# Quad_FC_power_V10_7-final.net
KiCad netlist of a schematic drawn in Altium Designer
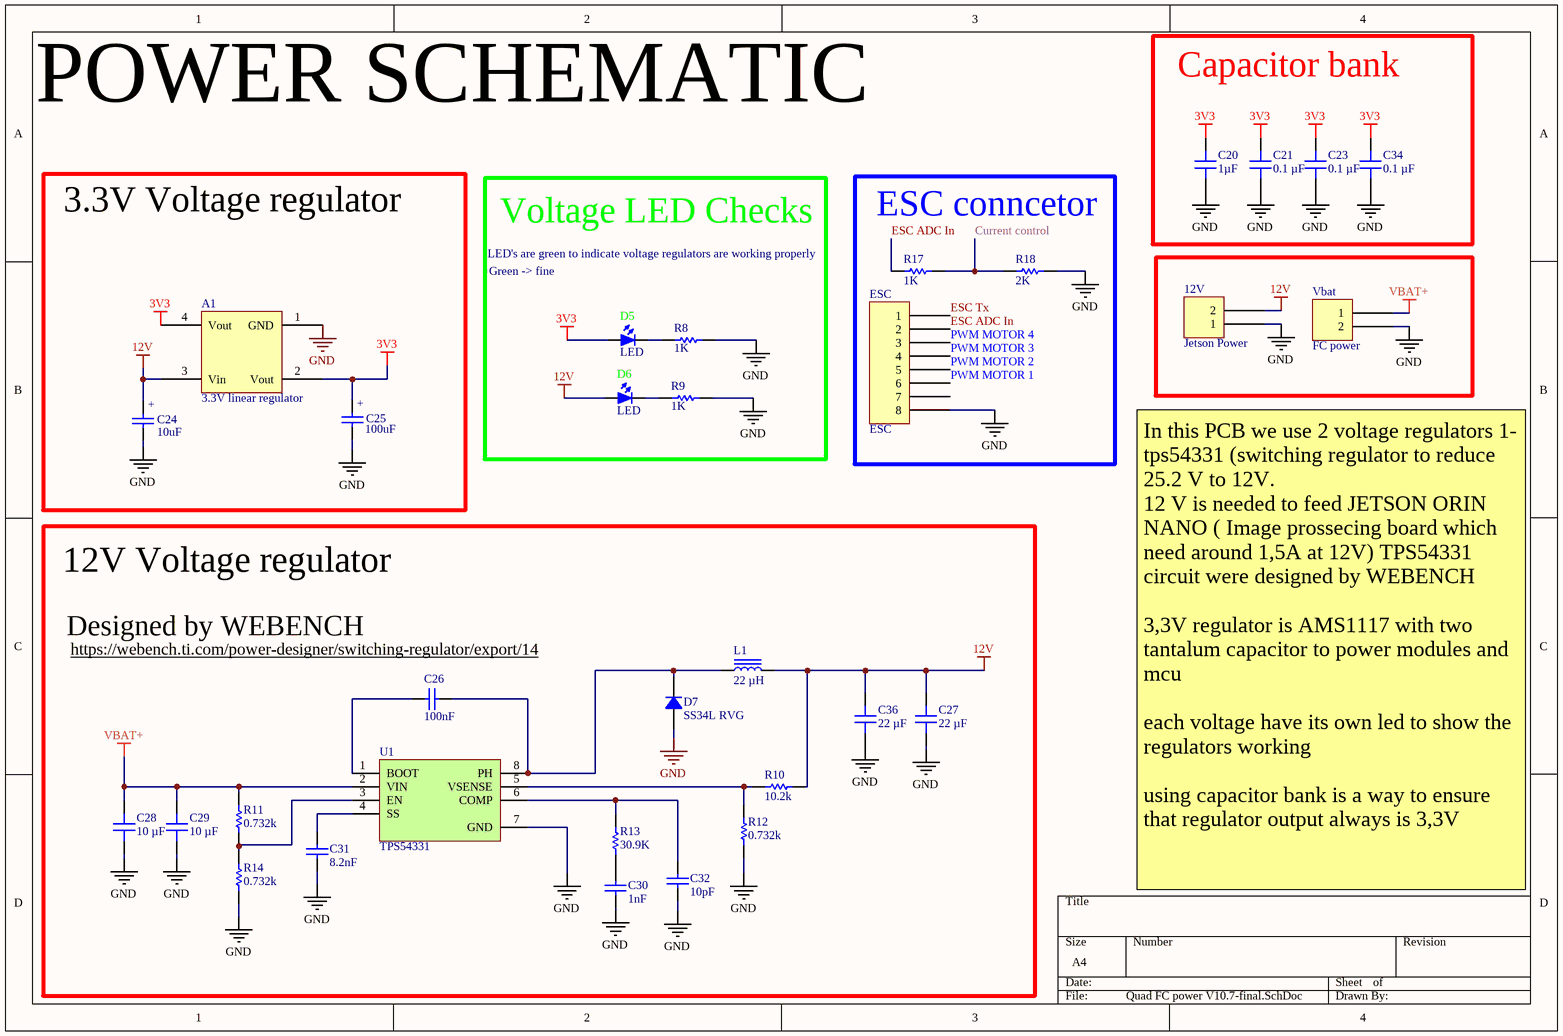
[diagram p0: Quad FC power V10.7-final.SchDoc]

(export (version "E")
  (design (tool "Eeschema 10.0.6"))
  (components
    (comp (ref "12V")
      (value "Jetson Power")
      (footprint "JST XH B2B-XH-A")
      (description "CONN HEADER VERT 2POS 2.5MM")
      (fields
        (field (name "PART NUMBER") "B2B-XH-A(LF)(SN)")
        (field (name "MANUFACTURER") "JST Sales America Inc.")
      )
      (libsource (lib "Celestial Altium Library - altium_library (1)") (part "2 Pin"))
    )
    (comp (ref "A1")
      (value "3.3V linear regulator")
      (footprint "SOT230P700X180-4N")
      (libsource (lib "Integrated_Library1") (part "ams1117"))
    )
    (comp (ref "C20")
      (value "1µF")
      (footprint "CAP 0805_2012")
      (description "CAP CER 1UF 10V X7R 0805")
      (fields (field (name "PART NUMBER") "MM05ZC105KCZ2A") (field (name "MANUFACTURER") "AVX Corporation"))
      (libsource (lib "Celestial Altium Library - altium_library (1)") (part "Capacitor"))
    )
    (comp (ref "C21")
      (value "0.1 µF")
      (footprint "CAP 0805_2012")
      (description "CAP CER 0.1UF 50V X7R 0805")
      (fields (field (name "PART NUMBER") "CC0805MRX7R9BB104") (field (name "MANUFACTURER") "Yageo"))
      (libsource (lib "Celestial Altium Library - altium_library (1)") (part "Capacitor"))
    )
    (comp (ref "C23")
      (value "0.1 µF")
      (footprint "CAP 0805_2012")
      (description "CAP CER 0.1UF 50V X7R 0805")
      (fields (field (name "PART NUMBER") "CC0805MRX7R9BB104") (field (name "MANUFACTURER") "Yageo"))
      (libsource (lib "Celestial Altium Library - altium_library (1)") (part "Capacitor"))
    )
    (comp (ref "C24")
      (value "10uF")
      (footprint "MY_CAP_SMD-B")
      (description "3.5X2.8MM")
      (libsource (lib "AMINLIB") (part "CAP_TANTAL_B"))
    )
    (comp (ref "C25")
      (value "100uF")
      (footprint "MY_CAP_SMD-B")
      (description "3.5X2.8MM")
      (libsource (lib "AMINLIB") (part "CAP_TANTAL_B"))
    )
    (comp (ref "C26")
      (value "100nF")
      (footprint "CAP0603")
      (description "F407VET6 Power CAP")
      (fields (field (name "DESIGNER") "Abbas Basereh"))
      (libsource (lib "2017AbbasBasereh9365731239 -ver1") (part "CAP SMD PACKAGE"))
    )
    (comp (ref "C27")
      (value "22 µF")
      (footprint "CAP 0805_2012")
      (description "CAP CER 10UF 50V X5R 0805")
      (fields
        (field (name "PART NUMBER") "GRM21BR61H106KE43K")
        (field (name "MANUFACTURER") "Murata Electronics")
      )
      (libsource (lib "Celestial Altium Library - altium_library (1)") (part "Capacitor"))
    )
    (comp (ref "C28")
      (value "10 µF")
      (footprint "CAP 0805_2012")
      (description "CAP CER 10UF 50V X5R 0805")
      (fields
        (field (name "PART NUMBER") "GRM21BR61H106KE43K")
        (field (name "MANUFACTURER") "Murata Electronics")
      )
      (libsource (lib "Celestial Altium Library - altium_library (1)") (part "Capacitor"))
    )
    (comp (ref "C29")
      (value "10 µF")
      (footprint "CAP 0805_2012")
      (description "CAP CER 10UF 50V X5R 0805")
      (fields
        (field (name "PART NUMBER") "GRM21BR61H106KE43K")
        (field (name "MANUFACTURER") "Murata Electronics")
      )
      (libsource (lib "Celestial Altium Library - altium_library (1)") (part "Capacitor"))
    )
    (comp (ref "C30")
      (value "1nF")
      (footprint "CAP0603")
      (description "F407VET6 Power CAP")
      (fields (field (name "DESIGNER") "Abbas Basereh"))
      (libsource (lib "2017AbbasBasereh9365731239 -ver1") (part "CAP SMD PACKAGE"))
    )
    (comp (ref "C31")
      (value "8.2nF")
      (footprint "CAP0603")
      (description "F407VET6 Power CAP")
      (fields (field (name "DESIGNER") "Abbas Basereh"))
      (libsource (lib "2017AbbasBasereh9365731239 -ver1") (part "CAP SMD PACKAGE"))
    )
    (comp (ref "C32")
      (value "10pF")
      (footprint "CAP0603")
      (description "F407VET6 Power CAP")
      (fields (field (name "DESIGNER") "Abbas Basereh"))
      (libsource (lib "2017AbbasBasereh9365731239 -ver1") (part "CAP SMD PACKAGE"))
    )
    (comp (ref "C34")
      (value "0.1 µF")
      (footprint "CAP 0805_2012")
      (description "CAP CER 0.1UF 50V X7R 0805")
      (fields (field (name "PART NUMBER") "CC0805MRX7R9BB104") (field (name "MANUFACTURER") "Yageo"))
      (libsource (lib "Celestial Altium Library - altium_library (1)") (part "Capacitor"))
    )
    (comp (ref "C36")
      (value "22 µF")
      (footprint "CAP 0805_2012")
      (description "CAP CER 10UF 50V X5R 0805")
      (fields
        (field (name "PART NUMBER") "GRM21BR61H106KE43K")
        (field (name "MANUFACTURER") "Murata Electronics")
      )
      (libsource (lib "Celestial Altium Library - altium_library (1)") (part "Capacitor"))
    )
    (comp (ref "D5")
      (value "LED")
      (footprint "0603 - LED")
      (description "Led")
      (fields (field (name "PUBLISHER") "Altium Limited"))
      (libsource (lib "Sajad_Altium_Library") (part "LED"))
    )
    (comp (ref "D6")
      (value "LED")
      (footprint "0603 - LED")
      (description "Led")
      (fields (field (name "PUBLISHER") "Altium Limited"))
      (libsource (lib "Sajad_Altium_Library") (part "LED"))
    )
    (comp (ref "D7")
      (value "SS34L RVG")
      (footprint "SMF DO-219AB")
      (description "DIODE SCHOTTKY 40V 3A SUB SMA")
      (fields (field (name "MANUFACTURER") "Taiwan Semiconductor Corporation"))
      (libsource (lib "Celestial Altium Library - altium_library (1)") (part "Diode"))
    )
    (comp (ref "ESC")
      (value "ESC")
      (footprint "JST SM08B-SRSS-TB")
      (description "CONN HEADER SMD R/A 8POS 1MM")
      (fields
        (field (name "PART NUMBER") "SM08B-SRSS-TB(LF)(SN)")
        (field (name "MANUFACTURER") "JST Sales America Inc.")
      )
      (libsource (lib "Celestial Altium Library - altium_library (1)") (part "8 Pin"))
    )
    (comp (ref "L1")
      (value "22 µH")
      (footprint "TAIYO YUDEN NRS8030")
      (description "FIXED IND 10UH 3A 42.9 MOHM SMD")
      (fields (field (name "PART NUMBER") "NRS8030T100MJGJV") (field (name "MANUFACTURER") "Taiyo Yuden"))
      (libsource (lib "Celestial Altium Library - altium_library (1)") (part "Inductor"))
    )
    (comp (ref "R8")
      (value "1K")
      (footprint "RES0603")
      (description "TOTAL SMD RESISTOR PACK")
      (fields (field (name "DESIGNER") "Abbas Basereh"))
      (libsource (lib "2017AbbasBasereh9365731239 -ver1") (part "RES SMD PACKAGE"))
    )
    (comp (ref "R9")
      (value "1K")
      (footprint "RES0603")
      (description "TOTAL SMD RESISTOR PACK")
      (fields (field (name "DESIGNER") "Abbas Basereh"))
      (libsource (lib "2017AbbasBasereh9365731239 -ver1") (part "RES SMD PACKAGE"))
    )
    (comp (ref "R10")
      (value "10.2k")
      (footprint "RES0603")
      (description "TOTAL SMD RESISTOR PACK")
      (fields (field (name "DESIGNER") "Abbas Basereh"))
      (libsource (lib "2017AbbasBasereh9365731239 -ver1") (part "RES SMD PACKAGE"))
    )
    (comp (ref "R11")
      (value "0.732k")
      (footprint "RES0603")
      (description "TOTAL SMD RESISTOR PACK")
      (fields (field (name "DESIGNER") "Abbas Basereh"))
      (libsource (lib "2017AbbasBasereh9365731239 -ver1") (part "RES SMD PACKAGE"))
    )
    (comp (ref "R12")
      (value "0.732k")
      (footprint "RES0603")
      (description "TOTAL SMD RESISTOR PACK")
      (fields (field (name "DESIGNER") "Abbas Basereh"))
      (libsource (lib "2017AbbasBasereh9365731239 -ver1") (part "RES SMD PACKAGE"))
    )
    (comp (ref "R13")
      (value "30.9K")
      (footprint "RES0603")
      (description "TOTAL SMD RESISTOR PACK")
      (fields (field (name "DESIGNER") "Abbas Basereh"))
      (libsource (lib "2017AbbasBasereh9365731239 -ver1") (part "RES SMD PACKAGE"))
    )
    (comp (ref "R14")
      (value "0.732k")
      (footprint "RES0603")
      (description "TOTAL SMD RESISTOR PACK")
      (fields (field (name "DESIGNER") "Abbas Basereh"))
      (libsource (lib "2017AbbasBasereh9365731239 -ver1") (part "RES SMD PACKAGE"))
    )
    (comp (ref "R17")
      (value "1K")
      (footprint "RES0603")
      (description "TOTAL SMD RESISTOR PACK")
      (fields (field (name "DESIGNER") "Abbas Basereh"))
      (libsource (lib "2017AbbasBasereh9365731239 -ver1") (part "RES SMD PACKAGE"))
    )
    (comp (ref "R18")
      (value "2K")
      (footprint "RES0603")
      (description "TOTAL SMD RESISTOR PACK")
      (fields (field (name "DESIGNER") "Abbas Basereh"))
      (libsource (lib "2017AbbasBasereh9365731239 -ver1") (part "RES SMD PACKAGE"))
    )
    (comp (ref "U1")
      (value "TPS54331")
      (footprint "SO8")
      (description "DC/DC Switching Regulators 2A,28V,1MHz Step Down SWIFT DC/D;Output Voltage:0.8 V to 25 V")
      (libsource (lib "Sajad_Altium_Library") (part "TPS54331"))
    )
    (comp (ref "Vbat")
      (value "FC power")
      (footprint "JST XH B2B-XH-A")
      (description "CONN HEADER VERT 2POS 2.5MM")
      (fields
        (field (name "PART NUMBER") "B2B-XH-A(LF)(SN)")
        (field (name "MANUFACTURER") "JST Sales America Inc.")
      )
      (libsource (lib "") (part "2 Pin_1"))
    )
  )
  (nets
    (net (code "1") (name "/Current control") (class "Default")
      (node (ref "R17") (pin "1") (pinfunction "1_1") (pintype "passive"))
      (node (ref "R18") (pin "2") (pinfunction "2_2") (pintype "passive"))
    )
    (net (code "2") (name "/ESC ADC In") (class "Default")
      (node (ref "ESC") (pin "2") (pinfunction "2_2") (pintype "passive"))
      (node (ref "R17") (pin "2") (pinfunction "2_2") (pintype "passive"))
    )
    (net (code "3") (name "/ESC Tx") (class "Default")
      (node (ref "ESC") (pin "1") (pinfunction "1_1") (pintype "passive"))
    )
    (net (code "4") (name "/PWM MOTOR 1") (class "Default")
      (node (ref "ESC") (pin "6") (pinfunction "6_6") (pintype "passive"))
    )
    (net (code "5") (name "/PWM MOTOR 2") (class "Default")
      (node (ref "ESC") (pin "5") (pinfunction "5_5") (pintype "passive"))
    )
    (net (code "6") (name "/PWM MOTOR 3") (class "Default")
      (node (ref "ESC") (pin "4") (pinfunction "4_4") (pintype "passive"))
    )
    (net (code "7") (name "/PWM MOTOR 4") (class "Default")
      (node (ref "ESC") (pin "3") (pinfunction "3_3") (pintype "passive"))
    )
    (net (code "8") (name "3V3") (class "Default")
      (node (ref "A1") (pin "2") (pinfunction "Vout_2") (pintype "passive"))
      (node (ref "A1") (pin "4") (pinfunction "Vout_4") (pintype "passive"))
      (node (ref "C20") (pin "2") (pinfunction "2_2") (pintype "passive"))
      (node (ref "C21") (pin "2") (pinfunction "2_2") (pintype "passive"))
      (node (ref "C23") (pin "2") (pinfunction "2_2") (pintype "passive"))
      (node (ref "C25") (pin "+") (pinfunction "+_+") (pintype "passive"))
      (node (ref "C34") (pin "2") (pinfunction "2_2") (pintype "passive"))
      (node (ref "D5") (pin "1") (pinfunction "A_1") (pintype "passive"))
    )
    (net (code "9") (name "12V") (class "Default")
      (node (ref "12V") (pin "2") (pinfunction "2_2") (pintype "passive"))
      (node (ref "A1") (pin "3") (pinfunction "Vin_3") (pintype "passive"))
      (node (ref "C24") (pin "+") (pinfunction "+_+") (pintype "passive"))
      (node (ref "C27") (pin "2") (pinfunction "2_2") (pintype "passive"))
      (node (ref "C36") (pin "2") (pinfunction "2_2") (pintype "passive"))
      (node (ref "D6") (pin "1") (pinfunction "A_1") (pintype "passive"))
      (node (ref "L1") (pin "2") (pinfunction "2_2") (pintype "passive"))
      (node (ref "R10") (pin "2") (pinfunction "2_2") (pintype "passive"))
    )
    (net (code "10") (name "GND") (class "Default")
      (node (ref "12V") (pin "1") (pinfunction "1_1") (pintype "passive"))
      (node (ref "A1") (pin "1") (pinfunction "GND_1") (pintype "passive"))
      (node (ref "C20") (pin "1") (pinfunction "1_1") (pintype "passive"))
      (node (ref "C21") (pin "1") (pinfunction "1_1") (pintype "passive"))
      (node (ref "C23") (pin "1") (pinfunction "1_1") (pintype "passive"))
      (node (ref "C24") (pin "-") (pinfunction "-_-") (pintype "passive"))
      (node (ref "C25") (pin "-") (pinfunction "-_-") (pintype "passive"))
      (node (ref "C27") (pin "1") (pinfunction "1_1") (pintype "passive"))
      (node (ref "C28") (pin "1") (pinfunction "1_1") (pintype "passive"))
      (node (ref "C29") (pin "1") (pinfunction "1_1") (pintype "passive"))
      (node (ref "C30") (pin "2") (pinfunction "2_2") (pintype "passive"))
      (node (ref "C31") (pin "2") (pinfunction "2_2") (pintype "passive"))
      (node (ref "C32") (pin "2") (pinfunction "2_2") (pintype "passive"))
      (node (ref "C34") (pin "1") (pinfunction "1_1") (pintype "passive"))
      (node (ref "C36") (pin "1") (pinfunction "1_1") (pintype "passive"))
      (node (ref "D7") (pin "1") (pinfunction "1_1") (pintype "passive"))
      (node (ref "ESC") (pin "8") (pinfunction "8_8") (pintype "passive"))
      (node (ref "R12") (pin "1") (pinfunction "1_1") (pintype "passive"))
      (node (ref "R14") (pin "1") (pinfunction "1_1") (pintype "passive"))
      (node (ref "R18") (pin "1") (pinfunction "1_1") (pintype "passive"))
      (node (ref "R8") (pin "2") (pinfunction "2_2") (pintype "passive"))
      (node (ref "R9") (pin "2") (pinfunction "2_2") (pintype "passive"))
      (node (ref "U1") (pin "7") (pinfunction "GND_7") (pintype "passive"))
      (node (ref "Vbat") (pin "2") (pinfunction "2_2") (pintype "passive"))
    )
    (net (code "11") (name "Net-(C30-Pad1)") (class "Default")
      (node (ref "C30") (pin "1") (pinfunction "1_1") (pintype "passive"))
      (node (ref "R13") (pin "1") (pinfunction "1_1") (pintype "passive"))
    )
    (net (code "12") (name "Net-(D5-K)") (class "Default")
      (node (ref "D5") (pin "2") (pinfunction "K_2") (pintype "passive"))
      (node (ref "R8") (pin "1") (pinfunction "1_1") (pintype "passive"))
    )
    (net (code "13") (name "Net-(D6-K)") (class "Default")
      (node (ref "D6") (pin "2") (pinfunction "K_2") (pintype "passive"))
      (node (ref "R9") (pin "1") (pinfunction "1_1") (pintype "passive"))
    )
    (net (code "14") (name "Net-(U1-BOOT)") (class "Default")
      (node (ref "C26") (pin "2") (pinfunction "2_2") (pintype "passive"))
      (node (ref "U1") (pin "1") (pinfunction "BOOT_1") (pintype "passive"))
    )
    (net (code "15") (name "Net-(U1-COMP)") (class "Default")
      (node (ref "C32") (pin "1") (pinfunction "1_1") (pintype "passive"))
      (node (ref "R13") (pin "2") (pinfunction "2_2") (pintype "passive"))
      (node (ref "U1") (pin "6") (pinfunction "COMP_6") (pintype "power_in"))
    )
    (net (code "16") (name "Net-(U1-EN)") (class "Default")
      (node (ref "R11") (pin "1") (pinfunction "1_1") (pintype "passive"))
      (node (ref "R14") (pin "2") (pinfunction "2_2") (pintype "passive"))
      (node (ref "U1") (pin "3") (pinfunction "EN_3") (pintype "passive"))
    )
    (net (code "17") (name "Net-(U1-PH)") (class "Default")
      (node (ref "C26") (pin "1") (pinfunction "1_1") (pintype "passive"))
      (node (ref "D7") (pin "2") (pinfunction "2_2") (pintype "passive"))
      (node (ref "L1") (pin "1") (pinfunction "1_1") (pintype "passive"))
      (node (ref "U1") (pin "8") (pinfunction "PH_8") (pintype "open_collector"))
    )
    (net (code "18") (name "Net-(U1-SS)") (class "Default")
      (node (ref "C31") (pin "1") (pinfunction "1_1") (pintype "passive"))
      (node (ref "U1") (pin "4") (pinfunction "SS_4") (pintype "power_in"))
    )
    (net (code "19") (name "Net-(U1-VSENSE)") (class "Default")
      (node (ref "R10") (pin "1") (pinfunction "1_1") (pintype "passive"))
      (node (ref "R12") (pin "2") (pinfunction "2_2") (pintype "passive"))
      (node (ref "U1") (pin "5") (pinfunction "VSENSE_5") (pintype "passive"))
    )
    (net (code "20") (name "VBAT+") (class "Default")
      (node (ref "C28") (pin "2") (pinfunction "2_2") (pintype "passive"))
      (node (ref "C29") (pin "2") (pinfunction "2_2") (pintype "passive"))
      (node (ref "R11") (pin "2") (pinfunction "2_2") (pintype "passive"))
      (node (ref "U1") (pin "2") (pinfunction "VIN_2") (pintype "passive"))
      (node (ref "Vbat") (pin "1") (pinfunction "1_1") (pintype "passive"))
    )
    (net (code "21") (name "unconnected-(ESC-Pad7)") (class "Default")
      (node (ref "ESC") (pin "7") (pinfunction "7_7") (pintype "passive"))
    )
  )
)
